# CAN.net
KiCad netlist of a schematic drawn in Altium Designer
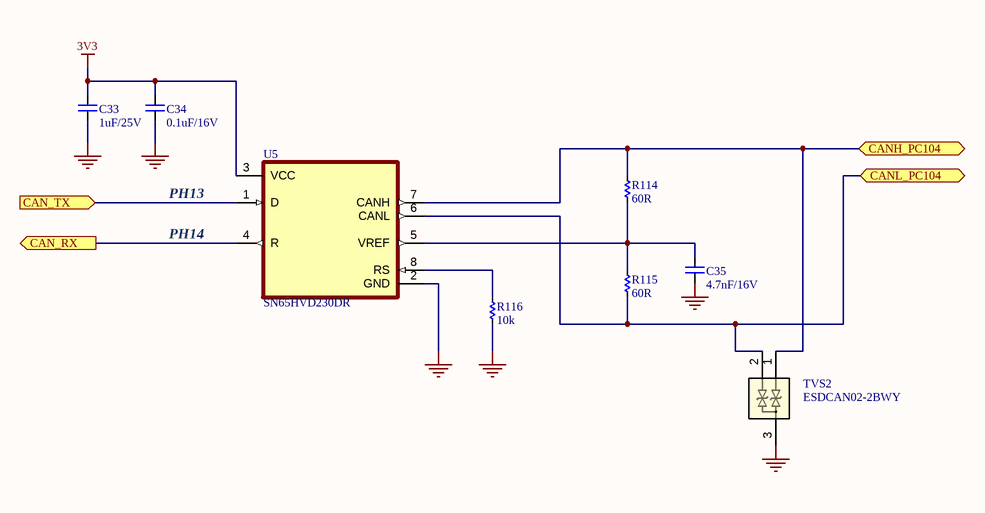
[diagram p0: CAN.SchDoc]

(export (version "E")
  (design (tool "Eeschema 10.0.6"))
  (components
    (comp (ref "C33")
      (value "1uF/25V")
      (footprint "CAP_C_1608X80")
      (description "CAP_Chip")
      (libsource (lib "LABLIB") (part "CAP_SMD"))
    )
    (comp (ref "C34")
      (value "0.1uF/16V")
      (footprint "CAP_C_1608X80")
      (description "CAP_Chip")
      (libsource (lib "LABLIB") (part "CAP_SMD"))
    )
    (comp (ref "C35")
      (value "4.7nF/16V")
      (footprint "CAP_C_1608X80")
      (description "CAP_Chip")
      (libsource (lib "LABLIB") (part "CAP_SMD"))
    )
    (comp (ref "R114")
      (value "60R")
      (footprint "RES_C_1608X60")
      (description "RES")
      (libsource (lib "LABLIB") (part "_RES_B_2"))
    )
    (comp (ref "R115")
      (value "60R")
      (footprint "RES_C_1608X60")
      (description "RES")
      (libsource (lib "LABLIB") (part "_RES_B_2"))
    )
    (comp (ref "R116")
      (value "10k")
      (footprint "RES_C_1608X60")
      (description "RES")
      (libsource (lib "LABLIB") (part "_RES_B_2"))
    )
    (comp (ref "TVS2")
      (value "ESDCAN02-2BWY")
      (footprint "SOT323-3L_STM")
      (description "Automotive dual-line TVS in SOT323-3L for CAN bus (12 V system)")
      (fields (field (name "COPYRIGHT") "Copyright (C) 2025 Ultra Librarian. All rights reserved."))
      (libsource (lib "COMM_SCHLIB") (part "ESDCAN02-2BWY"))
    )
    (comp (ref "U5")
      (value "SN65HVD230DR")
      (footprint "SOIC127P599X175-8N")
      (description "3.3 V CAN Transceiver with Standby Mode")
      (fields (field (name "MF") "Texas Instruments"))
      (libsource (lib "COMM_SCHLIB") (part "SN65HVD230DR"))
    )
  )
  (nets
    (net (code "1") (name "/CANH_PC104") (class "Default")
      (node (ref "R114") (pin "2") (pinfunction "2_2") (pintype "passive"))
      (node (ref "TVS2") (pin "1") (pinfunction "1_1") (pintype "passive"))
      (node (ref "U5") (pin "7") (pinfunction "CANH_7") (pintype "output"))
    )
    (net (code "2") (name "/CANL_PC104") (class "Default")
      (node (ref "R115") (pin "1") (pinfunction "1_1") (pintype "passive"))
      (node (ref "TVS2") (pin "2") (pinfunction "2_2") (pintype "passive"))
      (node (ref "U5") (pin "6") (pinfunction "CANL_6") (pintype "output"))
    )
    (net (code "3") (name "/CAN_RX") (class "Default")
      (node (ref "U5") (pin "4") (pinfunction "R_4") (pintype "output"))
    )
    (net (code "4") (name "/CAN_TX") (class "Default")
      (node (ref "U5") (pin "1") (pinfunction "D_1") (pintype "input"))
    )
    (net (code "5") (name "3V3") (class "Default")
      (node (ref "C33") (pin "1") (pinfunction "1_1") (pintype "passive"))
      (node (ref "C34") (pin "1") (pinfunction "1_1") (pintype "passive"))
      (node (ref "U5") (pin "3") (pinfunction "VCC_3") (pintype "power_in"))
    )
    (net (code "6") (name "GND") (class "Default")
      (node (ref "C33") (pin "2") (pinfunction "2_2") (pintype "passive"))
      (node (ref "C34") (pin "2") (pinfunction "2_2") (pintype "passive"))
      (node (ref "C35") (pin "2") (pinfunction "2_2") (pintype "passive"))
      (node (ref "R116") (pin "1") (pinfunction "1_1") (pintype "passive"))
      (node (ref "TVS2") (pin "3") (pinfunction "3_3") (pintype "passive"))
      (node (ref "U5") (pin "2") (pinfunction "GND_2") (pintype "power_in"))
    )
    (net (code "7") (name "Net-(U5-RS)") (class "Default")
      (node (ref "R116") (pin "2") (pinfunction "2_2") (pintype "passive"))
      (node (ref "U5") (pin "8") (pinfunction "RS_8") (pintype "input"))
    )
    (net (code "8") (name "Net-(U5-VREF)") (class "Default")
      (node (ref "C35") (pin "1") (pinfunction "1_1") (pintype "passive"))
      (node (ref "R114") (pin "1") (pinfunction "1_1") (pintype "passive"))
      (node (ref "R115") (pin "2") (pinfunction "2_2") (pintype "passive"))
      (node (ref "U5") (pin "5") (pinfunction "VREF_5") (pintype "output"))
    )
  )
)
